# differential_output_board.net
KiCad netlist of a schematic drawn in EAGLE
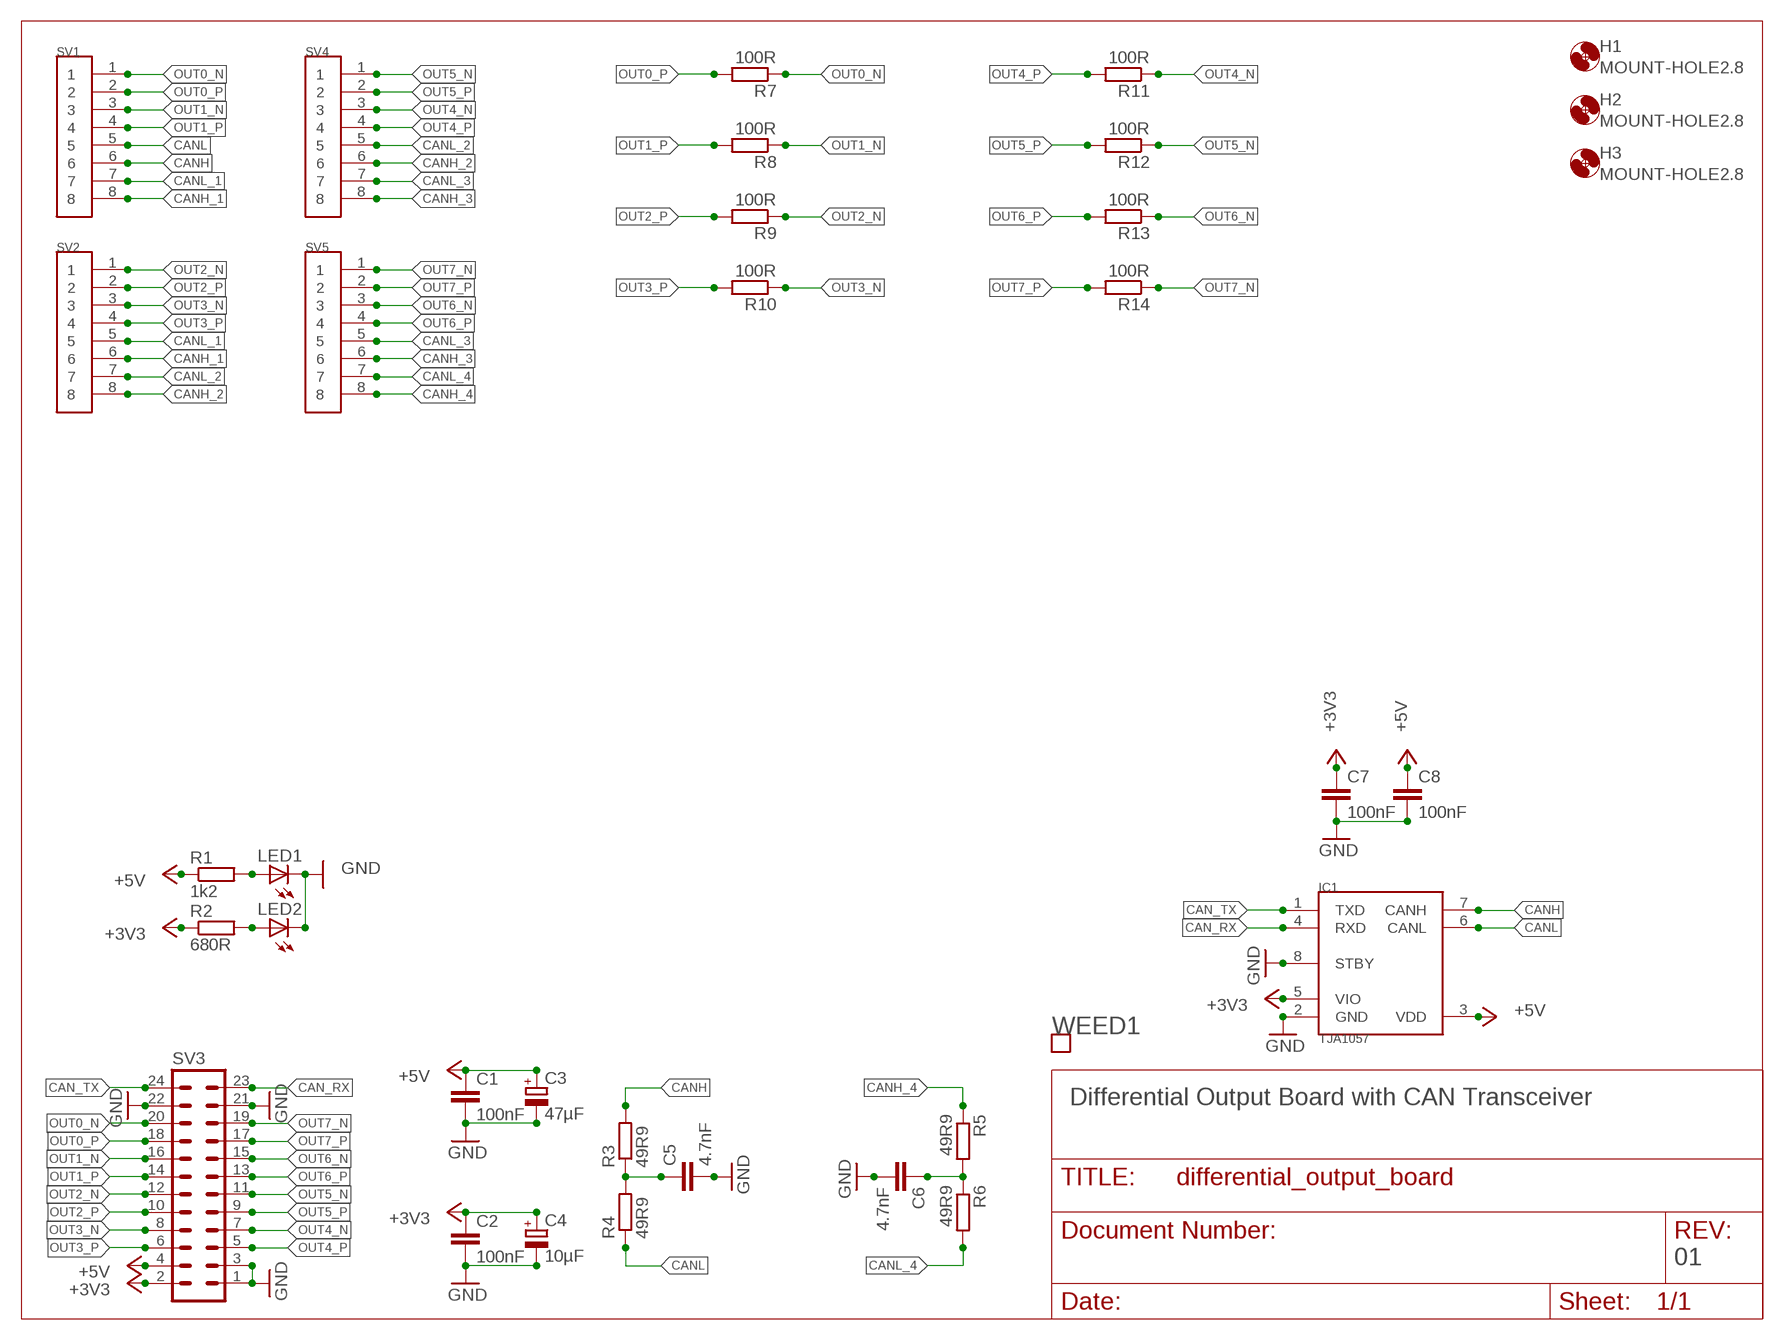
[diagram p0: schematic, sheet 1]

(export (version "E")
  (design (tool "Eeschema 10.0.6"))
  (components
    (comp (ref "C1")
      (value "100nF")
      (footprint "eagle-import:C0805")
      (libsource (lib "eagle-import") (part "C-EUC0805"))
    )
    (comp (ref "C2")
      (value "100nF")
      (footprint "eagle-import:C0805")
      (libsource (lib "eagle-import") (part "C-EUC0805"))
    )
    (comp (ref "C3")
      (value "47µF")
      (footprint "eagle-import:SMC_D")
      (libsource (lib "eagle-import") (part "CPOL-EUSMCD"))
    )
    (comp (ref "C4")
      (value "10µF")
      (footprint "eagle-import:SMC_B")
      (libsource (lib "eagle-import") (part "CPOL-EUSMCB"))
    )
    (comp (ref "C5")
      (value "4.7nF")
      (footprint "eagle-import:C0805")
      (libsource (lib "eagle-import") (part "C-EUC0805"))
    )
    (comp (ref "C6")
      (value "4.7nF")
      (footprint "eagle-import:C0805")
      (libsource (lib "eagle-import") (part "C-EUC0805"))
    )
    (comp (ref "C7")
      (value "100nF")
      (footprint "eagle-import:C0805")
      (libsource (lib "eagle-import") (part "C-EUC0805"))
    )
    (comp (ref "C8")
      (value "100nF")
      (footprint "eagle-import:C0805")
      (libsource (lib "eagle-import") (part "C-EUC0805"))
    )
    (comp (ref "H1")
      (value "MOUNT-HOLE2.8")
      (footprint "eagle-import:2,8")
      (libsource (lib "eagle-import") (part "MOUNT-HOLE2.8"))
    )
    (comp (ref "H2")
      (value "MOUNT-HOLE2.8")
      (footprint "eagle-import:2,8")
      (libsource (lib "eagle-import") (part "MOUNT-HOLE2.8"))
    )
    (comp (ref "H3")
      (value "MOUNT-HOLE2.8")
      (footprint "eagle-import:2,8")
      (libsource (lib "eagle-import") (part "MOUNT-HOLE2.8"))
    )
    (comp (ref "IC1")
      (value "TJA1057")
      (footprint "eagle-import:SOIC8")
      (libsource (lib "eagle-import") (part "TJA1057"))
    )
    (comp (ref "LED1")
      (value "LEDCHIPLED_1206")
      (footprint "eagle-import:CHIPLED_1206")
      (libsource (lib "eagle-import") (part "LEDCHIPLED_1206"))
    )
    (comp (ref "LED2")
      (value "LEDCHIPLED_1206")
      (footprint "eagle-import:CHIPLED_1206")
      (libsource (lib "eagle-import") (part "LEDCHIPLED_1206"))
    )
    (comp (ref "R1")
      (value "1k2")
      (footprint "eagle-import:M0805")
      (libsource (lib "eagle-import") (part "R-EU_M0805"))
    )
    (comp (ref "R2")
      (value "680R")
      (footprint "eagle-import:M0805")
      (libsource (lib "eagle-import") (part "R-EU_M0805"))
    )
    (comp (ref "R3")
      (value "49R9")
      (footprint "eagle-import:M1206")
      (libsource (lib "eagle-import") (part "R-EU_M1206"))
    )
    (comp (ref "R4")
      (value "49R9")
      (footprint "eagle-import:M1206")
      (libsource (lib "eagle-import") (part "R-EU_M1206"))
    )
    (comp (ref "R5")
      (value "49R9")
      (footprint "eagle-import:M1206")
      (libsource (lib "eagle-import") (part "R-EU_M1206"))
    )
    (comp (ref "R6")
      (value "49R9")
      (footprint "eagle-import:M1206")
      (libsource (lib "eagle-import") (part "R-EU_M1206"))
    )
    (comp (ref "R7")
      (value "100R")
      (footprint "eagle-import:M1206")
      (libsource (lib "eagle-import") (part "R-EU_M1206"))
    )
    (comp (ref "R8")
      (value "100R")
      (footprint "eagle-import:M1206")
      (libsource (lib "eagle-import") (part "R-EU_M1206"))
    )
    (comp (ref "R9")
      (value "100R")
      (footprint "eagle-import:M1206")
      (libsource (lib "eagle-import") (part "R-EU_M1206"))
    )
    (comp (ref "R10")
      (value "100R")
      (footprint "eagle-import:M1206")
      (libsource (lib "eagle-import") (part "R-EU_M1206"))
    )
    (comp (ref "R11")
      (value "100R")
      (footprint "eagle-import:M1206")
      (libsource (lib "eagle-import") (part "R-EU_M1206"))
    )
    (comp (ref "R12")
      (value "100R")
      (footprint "eagle-import:M1206")
      (libsource (lib "eagle-import") (part "R-EU_M1206"))
    )
    (comp (ref "R13")
      (value "100R")
      (footprint "eagle-import:M1206")
      (libsource (lib "eagle-import") (part "R-EU_M1206"))
    )
    (comp (ref "R14")
      (value "100R")
      (footprint "eagle-import:M1206")
      (libsource (lib "eagle-import") (part "R-EU_M1206"))
    )
    (comp (ref "SV1")
      (value "SS-51000-003")
      (footprint "eagle-import:SS-51000-003")
      (libsource (lib "eagle-import") (part "SS-51000-003"))
    )
    (comp (ref "SV2")
      (value "SS-51000-003")
      (footprint "eagle-import:SS-51000-003")
      (libsource (lib "eagle-import") (part "SS-51000-003"))
    )
    (comp (ref "SV3")
      (value "MA12-2")
      (footprint "eagle-import:MA12-2")
      (libsource (lib "eagle-import") (part "MA12-2"))
    )
    (comp (ref "SV4")
      (value "SS-51000-003")
      (footprint "eagle-import:SS-51000-003")
      (libsource (lib "eagle-import") (part "SS-51000-003"))
    )
    (comp (ref "SV5")
      (value "SS-51000-003")
      (footprint "eagle-import:SS-51000-003")
      (libsource (lib "eagle-import") (part "SS-51000-003"))
    )
    (comp (ref "WEED1")
      (value "WEED")
      (footprint "eagle-import:DOINK")
      (libsource (lib "eagle-import") (part "WEED"))
    )
  )
  (nets
    (net (code "1") (name "+3V3") (class "Default")
      (node (ref "C2") (pin "1") (pinfunction "1_1") (pintype "passive"))
      (node (ref "C4") (pin "+") (pinfunction "+_+") (pintype "passive"))
      (node (ref "C7") (pin "1") (pinfunction "1_1") (pintype "passive"))
      (node (ref "IC1") (pin "5") (pinfunction "VIO_5") (pintype "bidirectional"))
      (node (ref "R2") (pin "1") (pinfunction "1_1") (pintype "passive"))
      (node (ref "SV3") (pin "2") (pinfunction "2_2") (pintype "passive"))
    )
    (net (code "2") (name "+5V") (class "Default")
      (node (ref "C1") (pin "1") (pinfunction "1_1") (pintype "passive"))
      (node (ref "C3") (pin "+") (pinfunction "+_+") (pintype "passive"))
      (node (ref "C8") (pin "1") (pinfunction "1_1") (pintype "passive"))
      (node (ref "IC1") (pin "3") (pinfunction "VDD_3") (pintype "bidirectional"))
      (node (ref "R1") (pin "1") (pinfunction "1_1") (pintype "passive"))
      (node (ref "SV3") (pin "4") (pinfunction "4_4") (pintype "passive"))
    )
    (net (code "3") (name "CANH") (class "Default")
      (node (ref "IC1") (pin "7") (pinfunction "CANH_7") (pintype "bidirectional"))
      (node (ref "R3") (pin "2") (pinfunction "2_2") (pintype "passive"))
      (node (ref "SV1") (pin "6") (pinfunction "6_6") (pintype "passive"))
    )
    (net (code "4") (name "CANH_1") (class "Default")
      (node (ref "SV1") (pin "8") (pinfunction "8_8") (pintype "passive"))
      (node (ref "SV2") (pin "6") (pinfunction "6_6") (pintype "passive"))
    )
    (net (code "5") (name "CANH_2") (class "Default")
      (node (ref "SV2") (pin "8") (pinfunction "8_8") (pintype "passive"))
      (node (ref "SV4") (pin "6") (pinfunction "6_6") (pintype "passive"))
    )
    (net (code "6") (name "CANH_3") (class "Default")
      (node (ref "SV4") (pin "8") (pinfunction "8_8") (pintype "passive"))
      (node (ref "SV5") (pin "6") (pinfunction "6_6") (pintype "passive"))
    )
    (net (code "7") (name "CANH_4") (class "Default")
      (node (ref "R5") (pin "1") (pinfunction "1_1") (pintype "passive"))
      (node (ref "SV5") (pin "8") (pinfunction "8_8") (pintype "passive"))
    )
    (net (code "8") (name "CANL") (class "Default")
      (node (ref "IC1") (pin "6") (pinfunction "CANL_6") (pintype "bidirectional"))
      (node (ref "R4") (pin "1") (pinfunction "1_1") (pintype "passive"))
      (node (ref "SV1") (pin "5") (pinfunction "5_5") (pintype "passive"))
    )
    (net (code "9") (name "CANL_1") (class "Default")
      (node (ref "SV1") (pin "7") (pinfunction "7_7") (pintype "passive"))
      (node (ref "SV2") (pin "5") (pinfunction "5_5") (pintype "passive"))
    )
    (net (code "10") (name "CANL_2") (class "Default")
      (node (ref "SV2") (pin "7") (pinfunction "7_7") (pintype "passive"))
      (node (ref "SV4") (pin "5") (pinfunction "5_5") (pintype "passive"))
    )
    (net (code "11") (name "CANL_3") (class "Default")
      (node (ref "SV4") (pin "7") (pinfunction "7_7") (pintype "passive"))
      (node (ref "SV5") (pin "5") (pinfunction "5_5") (pintype "passive"))
    )
    (net (code "12") (name "CANL_4") (class "Default")
      (node (ref "R6") (pin "2") (pinfunction "2_2") (pintype "passive"))
      (node (ref "SV5") (pin "7") (pinfunction "7_7") (pintype "passive"))
    )
    (net (code "13") (name "CAN_RX") (class "Default")
      (node (ref "IC1") (pin "4") (pinfunction "RXD_4") (pintype "bidirectional"))
      (node (ref "SV3") (pin "23") (pinfunction "23_23") (pintype "passive"))
    )
    (net (code "14") (name "CAN_TX") (class "Default")
      (node (ref "IC1") (pin "1") (pinfunction "TXD_1") (pintype "bidirectional"))
      (node (ref "SV3") (pin "24") (pinfunction "24_24") (pintype "passive"))
    )
    (net (code "15") (name "GND") (class "Default")
      (node (ref "C1") (pin "2") (pinfunction "2_2") (pintype "passive"))
      (node (ref "C2") (pin "2") (pinfunction "2_2") (pintype "passive"))
      (node (ref "C3") (pin "-") (pinfunction "-_-") (pintype "passive"))
      (node (ref "C4") (pin "-") (pinfunction "-_-") (pintype "passive"))
      (node (ref "C5") (pin "2") (pinfunction "2_2") (pintype "passive"))
      (node (ref "C6") (pin "2") (pinfunction "2_2") (pintype "passive"))
      (node (ref "C7") (pin "2") (pinfunction "2_2") (pintype "passive"))
      (node (ref "C8") (pin "2") (pinfunction "2_2") (pintype "passive"))
      (node (ref "IC1") (pin "2") (pinfunction "GND_2") (pintype "bidirectional"))
      (node (ref "IC1") (pin "8") (pinfunction "STBY_8") (pintype "bidirectional"))
      (node (ref "LED1") (pin "C") (pinfunction "C_C") (pintype "passive"))
      (node (ref "LED2") (pin "C") (pinfunction "C_C") (pintype "passive"))
      (node (ref "SV3") (pin "1") (pinfunction "1_1") (pintype "passive"))
      (node (ref "SV3") (pin "21") (pinfunction "21_21") (pintype "passive"))
      (node (ref "SV3") (pin "22") (pinfunction "22_22") (pintype "passive"))
      (node (ref "SV3") (pin "3") (pinfunction "3_3") (pintype "passive"))
    )
    (net (code "16") (name "Net-(C5-Pad1)") (class "Default")
      (node (ref "C5") (pin "1") (pinfunction "1_1") (pintype "passive"))
      (node (ref "R3") (pin "1") (pinfunction "1_1") (pintype "passive"))
      (node (ref "R4") (pin "2") (pinfunction "2_2") (pintype "passive"))
    )
    (net (code "17") (name "Net-(C6-Pad1)") (class "Default")
      (node (ref "C6") (pin "1") (pinfunction "1_1") (pintype "passive"))
      (node (ref "R5") (pin "2") (pinfunction "2_2") (pintype "passive"))
      (node (ref "R6") (pin "1") (pinfunction "1_1") (pintype "passive"))
    )
    (net (code "18") (name "Net-(LED1-PadA)") (class "Default")
      (node (ref "LED1") (pin "A") (pinfunction "A_A") (pintype "passive"))
      (node (ref "R1") (pin "2") (pinfunction "2_2") (pintype "passive"))
    )
    (net (code "19") (name "Net-(LED2-PadA)") (class "Default")
      (node (ref "LED2") (pin "A") (pinfunction "A_A") (pintype "passive"))
      (node (ref "R2") (pin "2") (pinfunction "2_2") (pintype "passive"))
    )
    (net (code "20") (name "OUT0_N") (class "Default")
      (node (ref "R7") (pin "1") (pinfunction "1_1") (pintype "passive"))
      (node (ref "SV1") (pin "1") (pinfunction "1_1") (pintype "passive"))
      (node (ref "SV3") (pin "20") (pinfunction "20_20") (pintype "passive"))
    )
    (net (code "21") (name "OUT0_P") (class "Default")
      (node (ref "R7") (pin "2") (pinfunction "2_2") (pintype "passive"))
      (node (ref "SV1") (pin "2") (pinfunction "2_2") (pintype "passive"))
      (node (ref "SV3") (pin "18") (pinfunction "18_18") (pintype "passive"))
    )
    (net (code "22") (name "OUT1_N") (class "Default")
      (node (ref "R8") (pin "1") (pinfunction "1_1") (pintype "passive"))
      (node (ref "SV1") (pin "3") (pinfunction "3_3") (pintype "passive"))
      (node (ref "SV3") (pin "16") (pinfunction "16_16") (pintype "passive"))
    )
    (net (code "23") (name "OUT1_P") (class "Default")
      (node (ref "R8") (pin "2") (pinfunction "2_2") (pintype "passive"))
      (node (ref "SV1") (pin "4") (pinfunction "4_4") (pintype "passive"))
      (node (ref "SV3") (pin "14") (pinfunction "14_14") (pintype "passive"))
    )
    (net (code "24") (name "OUT2_N") (class "Default")
      (node (ref "R9") (pin "1") (pinfunction "1_1") (pintype "passive"))
      (node (ref "SV2") (pin "1") (pinfunction "1_1") (pintype "passive"))
      (node (ref "SV3") (pin "12") (pinfunction "12_12") (pintype "passive"))
    )
    (net (code "25") (name "OUT2_P") (class "Default")
      (node (ref "R9") (pin "2") (pinfunction "2_2") (pintype "passive"))
      (node (ref "SV2") (pin "2") (pinfunction "2_2") (pintype "passive"))
      (node (ref "SV3") (pin "10") (pinfunction "10_10") (pintype "passive"))
    )
    (net (code "26") (name "OUT3_N") (class "Default")
      (node (ref "R10") (pin "1") (pinfunction "1_1") (pintype "passive"))
      (node (ref "SV2") (pin "3") (pinfunction "3_3") (pintype "passive"))
      (node (ref "SV3") (pin "8") (pinfunction "8_8") (pintype "passive"))
    )
    (net (code "27") (name "OUT3_P") (class "Default")
      (node (ref "R10") (pin "2") (pinfunction "2_2") (pintype "passive"))
      (node (ref "SV2") (pin "4") (pinfunction "4_4") (pintype "passive"))
      (node (ref "SV3") (pin "6") (pinfunction "6_6") (pintype "passive"))
    )
    (net (code "28") (name "OUT4_N") (class "Default")
      (node (ref "R11") (pin "1") (pinfunction "1_1") (pintype "passive"))
      (node (ref "SV3") (pin "7") (pinfunction "7_7") (pintype "passive"))
      (node (ref "SV4") (pin "3") (pinfunction "3_3") (pintype "passive"))
    )
    (net (code "29") (name "OUT4_P") (class "Default")
      (node (ref "R11") (pin "2") (pinfunction "2_2") (pintype "passive"))
      (node (ref "SV3") (pin "5") (pinfunction "5_5") (pintype "passive"))
      (node (ref "SV4") (pin "4") (pinfunction "4_4") (pintype "passive"))
    )
    (net (code "30") (name "OUT5_N") (class "Default")
      (node (ref "R12") (pin "1") (pinfunction "1_1") (pintype "passive"))
      (node (ref "SV3") (pin "11") (pinfunction "11_11") (pintype "passive"))
      (node (ref "SV4") (pin "1") (pinfunction "1_1") (pintype "passive"))
    )
    (net (code "31") (name "OUT5_P") (class "Default")
      (node (ref "R12") (pin "2") (pinfunction "2_2") (pintype "passive"))
      (node (ref "SV3") (pin "9") (pinfunction "9_9") (pintype "passive"))
      (node (ref "SV4") (pin "2") (pinfunction "2_2") (pintype "passive"))
    )
    (net (code "32") (name "OUT6_N") (class "Default")
      (node (ref "R13") (pin "1") (pinfunction "1_1") (pintype "passive"))
      (node (ref "SV3") (pin "15") (pinfunction "15_15") (pintype "passive"))
      (node (ref "SV5") (pin "3") (pinfunction "3_3") (pintype "passive"))
    )
    (net (code "33") (name "OUT6_P") (class "Default")
      (node (ref "R13") (pin "2") (pinfunction "2_2") (pintype "passive"))
      (node (ref "SV3") (pin "13") (pinfunction "13_13") (pintype "passive"))
      (node (ref "SV5") (pin "4") (pinfunction "4_4") (pintype "passive"))
    )
    (net (code "34") (name "OUT7_N") (class "Default")
      (node (ref "R14") (pin "1") (pinfunction "1_1") (pintype "passive"))
      (node (ref "SV3") (pin "19") (pinfunction "19_19") (pintype "passive"))
      (node (ref "SV5") (pin "1") (pinfunction "1_1") (pintype "passive"))
    )
    (net (code "35") (name "OUT7_P") (class "Default")
      (node (ref "R14") (pin "2") (pinfunction "2_2") (pintype "passive"))
      (node (ref "SV3") (pin "17") (pinfunction "17_17") (pintype "passive"))
      (node (ref "SV5") (pin "2") (pinfunction "2_2") (pintype "passive"))
    )
  )
)
